# SCH_CH1616ADX_2022-05-06.net
KiCad netlist of a schematic drawn in EasyEDA
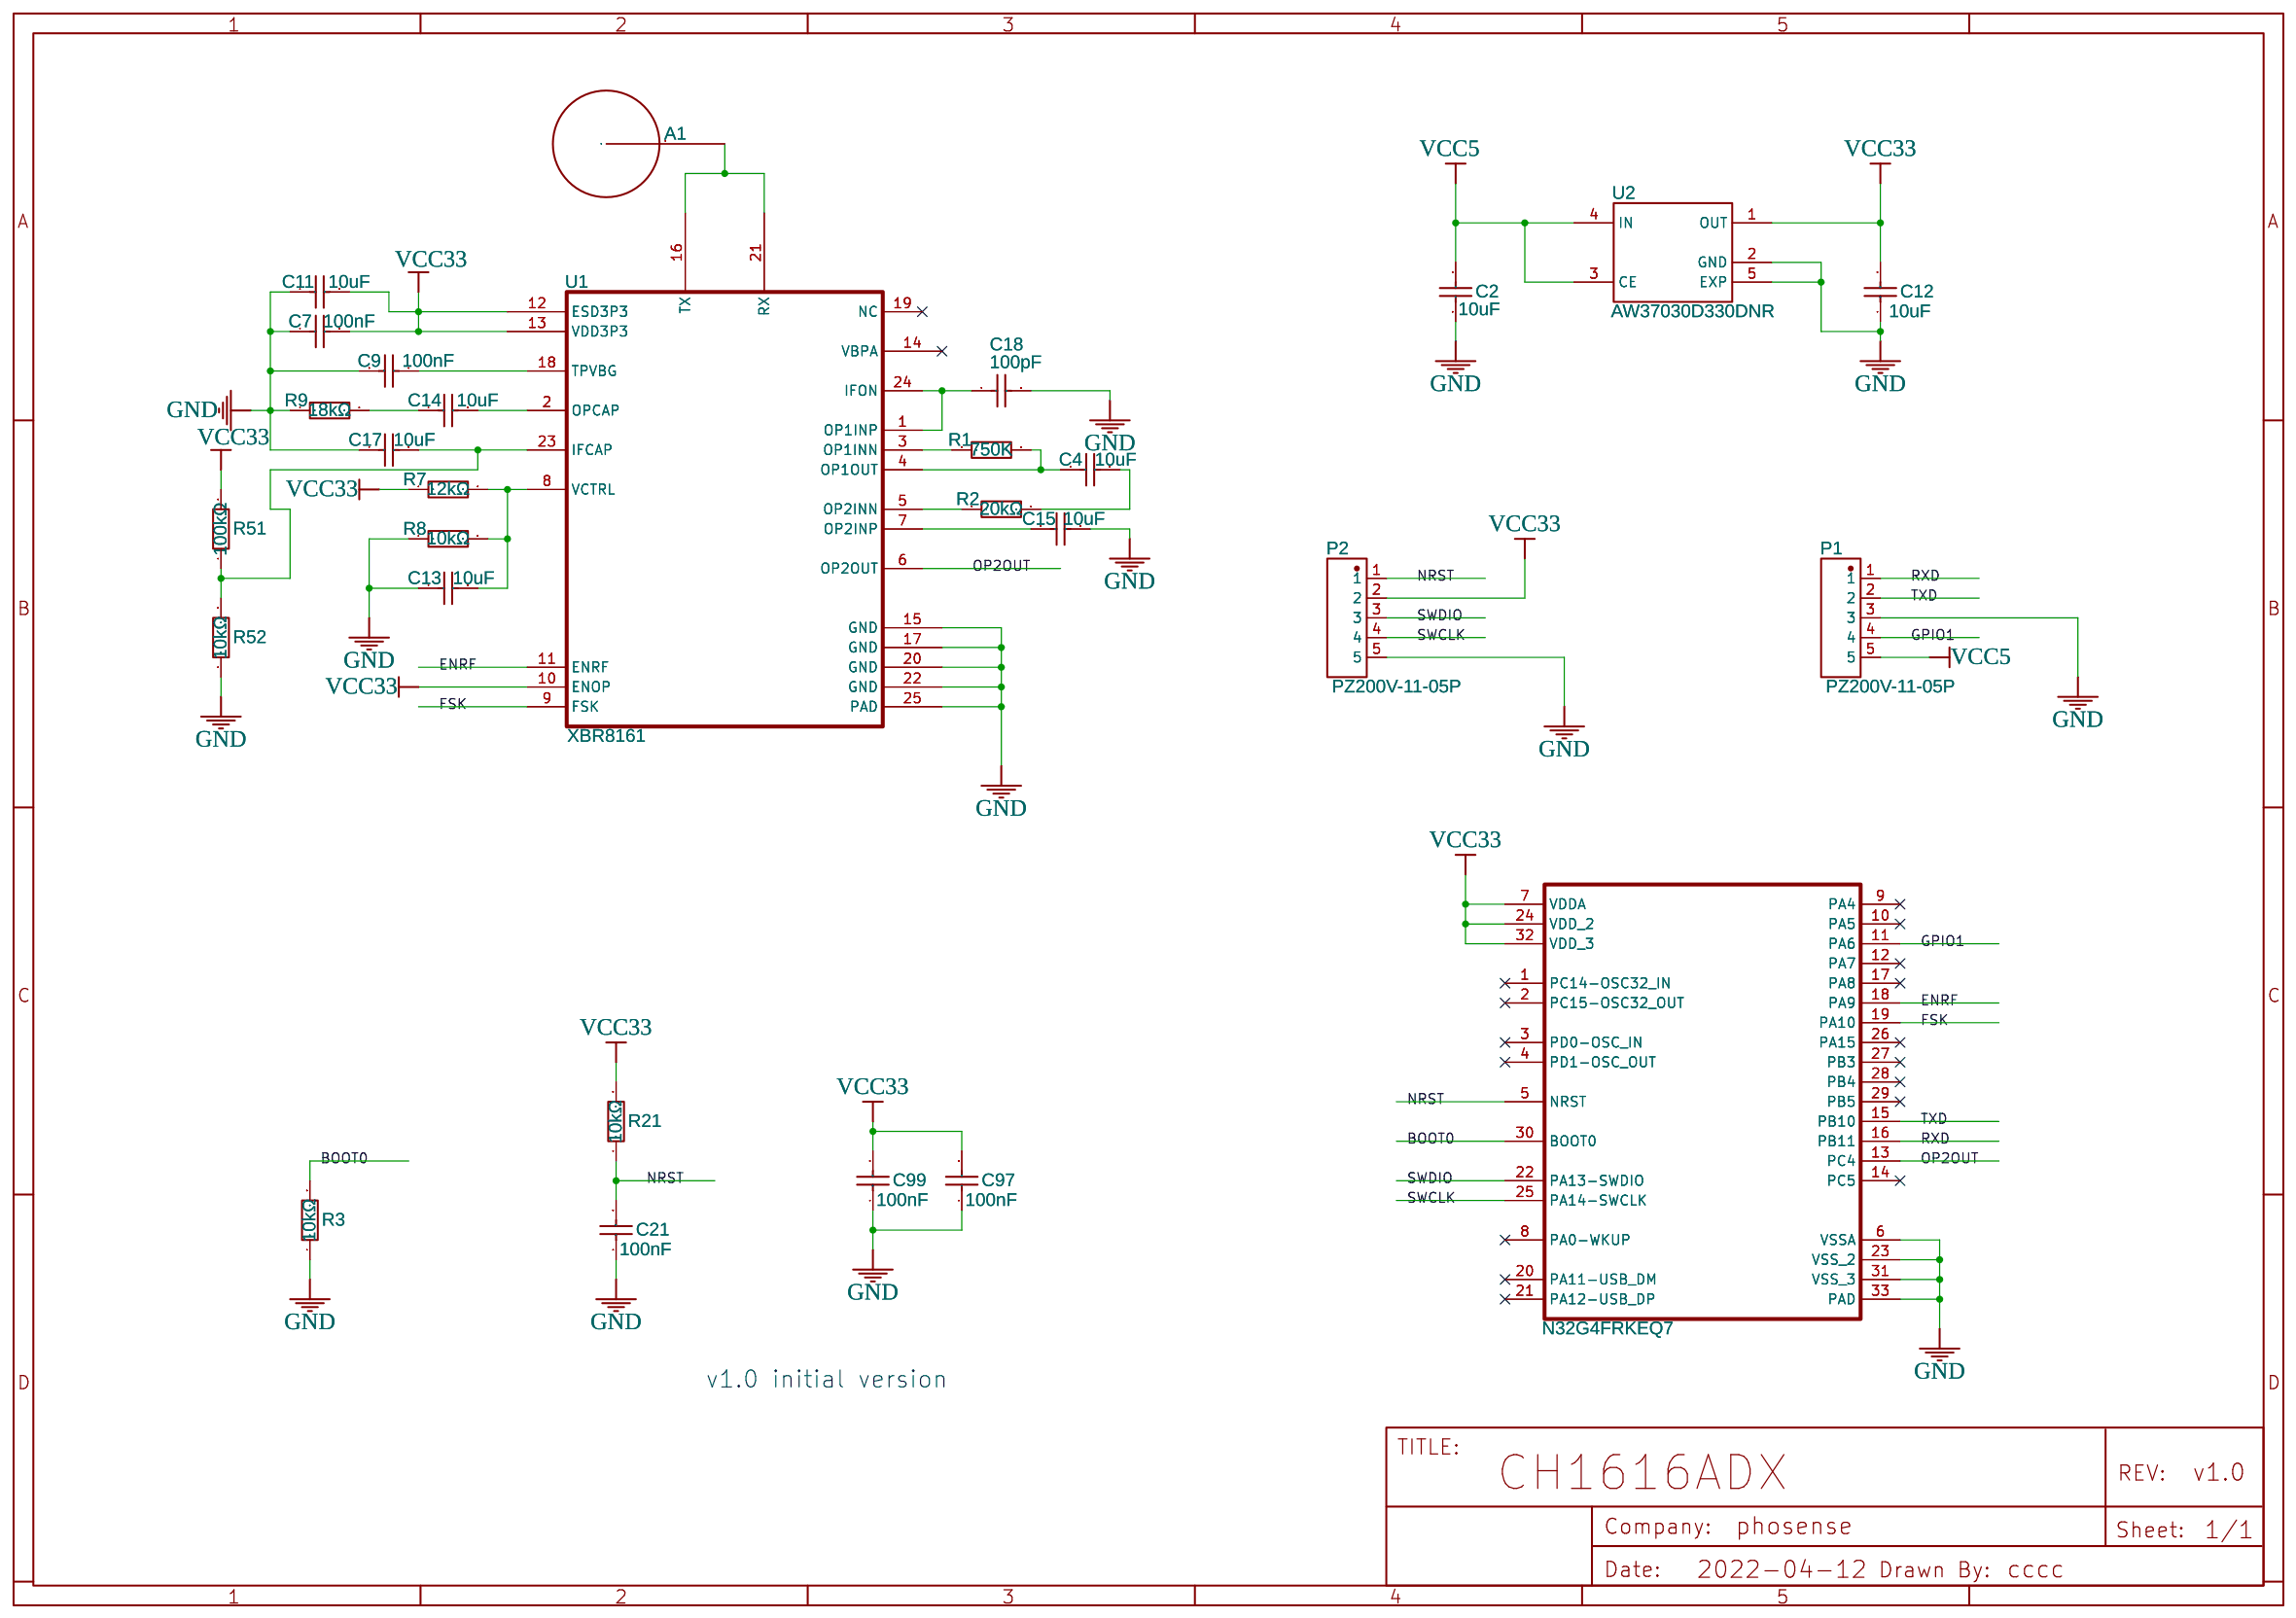
[diagram p0: schematic sheet]

(export (version "E")
  (design (tool "Eeschema 10.0.6"))
  (components
    (comp (ref "A1") (value "ar_10.525G") (libsource (lib "") (part "ar_10.525G")))
    (comp (ref "C2")
      (value "10uF")
      (fields
        (field (name "BOM_Manufacturer Part") "CL05A106MQ5NUNC")
        (field (name "BOM_Supplier Part") "C15525")
      )
      (libsource (lib "") (part "CL05A106MQ5NUNC_2"))
    )
    (comp (ref "C4")
      (value "10uF")
      (fields
        (field (name "BOM_Manufacturer Part") "CL05A106MQ5NUNC")
        (field (name "BOM_Supplier Part") "C15525")
      )
      (libsource (lib "") (part "CL05A106MQ5NUNC_1"))
    )
    (comp (ref "C7")
      (value "100nF")
      (fields
        (field (name "BOM_Manufacturer Part") "CL05B104KO5NNNC")
        (field (name "BOM_Supplier Part") "C1525")
      )
      (libsource (lib "") (part "CL05B104KO5NNNC_2"))
    )
    (comp (ref "C9")
      (value "100nF")
      (fields
        (field (name "BOM_Manufacturer Part") "CL05B104KO5NNNC")
        (field (name "BOM_Supplier Part") "C1525")
      )
      (libsource (lib "") (part "CL05B104KO5NNNC_1"))
    )
    (comp (ref "C11")
      (value "10uF")
      (fields
        (field (name "BOM_Manufacturer Part") "CL05A106MQ5NUNC")
        (field (name "BOM_Supplier Part") "C15525")
      )
      (libsource (lib "") (part "CL05A106MQ5NUNC_1"))
    )
    (comp (ref "C12")
      (value "10uF")
      (fields
        (field (name "BOM_Manufacturer Part") "CL05A106MQ5NUNC")
        (field (name "BOM_Supplier Part") "C15525")
      )
      (libsource (lib "") (part "CL05A106MQ5NUNC"))
    )
    (comp (ref "C13")
      (value "10uF")
      (fields
        (field (name "BOM_Manufacturer Part") "CL05A106MQ5NUNC")
        (field (name "BOM_Supplier Part") "C15525")
      )
      (libsource (lib "") (part "CL05A106MQ5NUNC_1"))
    )
    (comp (ref "C14")
      (value "10uF")
      (fields
        (field (name "BOM_Manufacturer Part") "CL05A106MQ5NUNC")
        (field (name "BOM_Supplier Part") "C15525")
      )
      (libsource (lib "") (part "CL05A106MQ5NUNC_1"))
    )
    (comp (ref "C15")
      (value "10uF")
      (fields
        (field (name "BOM_Manufacturer Part") "CL05A106MQ5NUNC")
        (field (name "BOM_Supplier Part") "C15525")
      )
      (libsource (lib "") (part "CL05A106MQ5NUNC_1"))
    )
    (comp (ref "C17")
      (value "10uF")
      (fields
        (field (name "BOM_Manufacturer Part") "CL05A106MQ5NUNC")
        (field (name "BOM_Supplier Part") "C15525")
      )
      (libsource (lib "") (part "CL05A106MQ5NUNC_1"))
    )
    (comp (ref "C18")
      (value "100pF")
      (fields
        (field (name "BOM_Manufacturer Part") "0402CG101J500NT")
        (field (name "BOM_Supplier Part") "C1546")
      )
      (libsource (lib "") (part "0402CG101J500NT"))
    )
    (comp (ref "C21")
      (value "100nF")
      (fields
        (field (name "BOM_Manufacturer Part") "CL05B104KO5NNNC")
        (field (name "BOM_Supplier Part") "C1525")
      )
      (libsource (lib "") (part "CL05B104KO5NNNC"))
    )
    (comp (ref "C97")
      (value "100nF")
      (fields
        (field (name "BOM_Manufacturer Part") "CL05B104KO5NNNC")
        (field (name "BOM_Supplier Part") "C1525")
      )
      (libsource (lib "") (part "CL05B104KO5NNNC"))
    )
    (comp (ref "C99")
      (value "100nF")
      (fields
        (field (name "BOM_Manufacturer Part") "CL05B104KO5NNNC")
        (field (name "BOM_Supplier Part") "C1525")
      )
      (libsource (lib "") (part "CL05B104KO5NNNC"))
    )
    (comp (ref "NO1") (value "N32G4FRKEQ7") (libsource (lib "") (part "N32G4FRKEQ7")))
    (comp (ref "P1")
      (value "PZ200V-11-05P")
      (fields (field (name "BOM_Supplier Part") "C541859"))
      (libsource (lib "") (part "PZ200V-11-05P"))
    )
    (comp (ref "P2")
      (value "PZ200V-11-05P")
      (fields (field (name "BOM_Supplier Part") "C541859"))
      (libsource (lib "") (part "PZ200V-11-05P"))
    )
    (comp (ref "R1")
      (value "750K")
      (fields
        (field (name "BOM_Manufacturer Part") "AC0402JR-07750KL")
        (field (name "BOM_Supplier Part") "C227414")
      )
      (libsource (lib "") (part "AC0402JR-07750KL"))
    )
    (comp (ref "R2")
      (value "20kΩ")
      (fields
        (field (name "BOM_Manufacturer Part") "0402WGF2002TCE")
        (field (name "BOM_Supplier Part") "C25765")
      )
      (libsource (lib "") (part "0402WGF2002TCE"))
    )
    (comp (ref "R3")
      (value "10kΩ")
      (fields
        (field (name "BOM_Manufacturer Part") "0402WGF1002TCE")
        (field (name "BOM_Supplier Part") "C25744")
      )
      (libsource (lib "") (part "0402WGF1002TCE"))
    )
    (comp (ref "R7")
      (value "12kΩ")
      (fields
        (field (name "BOM_Manufacturer Part") "0402WGF1202TCE")
        (field (name "BOM_Supplier Part") "C25752")
      )
      (libsource (lib "") (part "0402WGF1202TCE"))
    )
    (comp (ref "R8")
      (value "10kΩ")
      (fields
        (field (name "BOM_Manufacturer Part") "0402WGF1002TCE")
        (field (name "BOM_Supplier Part") "C25744")
      )
      (libsource (lib "") (part "0402WGF1002TCE_1"))
    )
    (comp (ref "R9")
      (value "18kΩ")
      (fields
        (field (name "BOM_Manufacturer Part") "0402WGF1802TCE")
        (field (name "BOM_Supplier Part") "C25762")
      )
      (libsource (lib "") (part "0402WGF1802TCE"))
    )
    (comp (ref "R21")
      (value "10kΩ")
      (fields
        (field (name "BOM_Manufacturer Part") "0402WGF1002TCE")
        (field (name "BOM_Supplier Part") "C25744")
      )
      (libsource (lib "") (part "0402WGF1002TCE"))
    )
    (comp (ref "R51")
      (value "100kΩ")
      (fields
        (field (name "BOM_Manufacturer Part") "0402WGF1003TCE")
        (field (name "BOM_Supplier Part") "C25741")
      )
      (libsource (lib "") (part "0402WGF1003TCE"))
    )
    (comp (ref "R52")
      (value "10kΩ")
      (fields
        (field (name "BOM_Manufacturer Part") "0402WGF1002TCE")
        (field (name "BOM_Supplier Part") "C25744")
      )
      (libsource (lib "") (part "0402WGF1002TCE"))
    )
    (comp (ref "U1") (value "XBR8161") (libsource (lib "") (part "XBR8161")))
    (comp (ref "U2") (value "AW37030D330DNR") (libsource (lib "") (part "AW37030D330DNR")))
  )
  (nets
    (net (code "1") (name "/BOOT0") (class "Default")
      (node (ref "NO1") (pin "30") (pinfunction "BOOT0_30") (pintype "unspecified"))
      (node (ref "R3") (pin "2") (pinfunction "2_2") (pintype "input"))
    )
    (net (code "2") (name "/ENRF") (class "Default")
      (node (ref "NO1") (pin "18") (pinfunction "PA9_18") (pintype "unspecified"))
      (node (ref "U1") (pin "11") (pinfunction "ENRF_11") (pintype "unspecified"))
    )
    (net (code "3") (name "/FSK") (class "Default")
      (node (ref "NO1") (pin "19") (pinfunction "PA10_19") (pintype "unspecified"))
      (node (ref "U1") (pin "9") (pinfunction "FSK_9") (pintype "unspecified"))
    )
    (net (code "4") (name "/GPIO1") (class "Default")
      (node (ref "NO1") (pin "11") (pinfunction "PA6_11") (pintype "unspecified"))
      (node (ref "P1") (pin "4") (pinfunction "4_4") (pintype "unspecified"))
    )
    (net (code "5") (name "/NRST") (class "Default")
      (node (ref "C21") (pin "2") (pinfunction "2_2") (pintype "input"))
      (node (ref "NO1") (pin "5") (pinfunction "NRST_5") (pintype "input"))
      (node (ref "P2") (pin "1") (pinfunction "1_1") (pintype "unspecified"))
      (node (ref "R21") (pin "1") (pinfunction "1_1") (pintype "input"))
    )
    (net (code "6") (name "/OP2OUT") (class "Default")
      (node (ref "NO1") (pin "13") (pinfunction "PC4_13") (pintype "unspecified"))
      (node (ref "U1") (pin "6") (pinfunction "OP2OUT_6") (pintype "unspecified"))
    )
    (net (code "7") (name "/RXD") (class "Default")
      (node (ref "NO1") (pin "16") (pinfunction "PB11_16") (pintype "unspecified"))
      (node (ref "P1") (pin "1") (pinfunction "1_1") (pintype "unspecified"))
    )
    (net (code "8") (name "/SWCLK") (class "Default")
      (node (ref "NO1") (pin "25") (pinfunction "PA14-SWCLK_25") (pintype "unspecified"))
      (node (ref "P2") (pin "4") (pinfunction "4_4") (pintype "unspecified"))
    )
    (net (code "9") (name "/SWDIO") (class "Default")
      (node (ref "NO1") (pin "22") (pinfunction "PA13-SWDIO_22") (pintype "unspecified"))
      (node (ref "P2") (pin "3") (pinfunction "3_3") (pintype "unspecified"))
    )
    (net (code "10") (name "/TXD") (class "Default")
      (node (ref "NO1") (pin "15") (pinfunction "PB10_15") (pintype "unspecified"))
      (node (ref "P1") (pin "2") (pinfunction "2_2") (pintype "unspecified"))
    )
    (net (code "11") (name "GND") (class "Default")
      (node (ref "C11") (pin "1") (pinfunction "1_1") (pintype "input"))
      (node (ref "C12") (pin "1") (pinfunction "1_1") (pintype "input"))
      (node (ref "C13") (pin "1") (pinfunction "1_1") (pintype "input"))
      (node (ref "C15") (pin "2") (pinfunction "2_2") (pintype "input"))
      (node (ref "C17") (pin "1") (pinfunction "1_1") (pintype "input"))
      (node (ref "C18") (pin "2") (pinfunction "2_2") (pintype "input"))
      (node (ref "C2") (pin "2") (pinfunction "2_2") (pintype "input"))
      (node (ref "C21") (pin "1") (pinfunction "1_1") (pintype "input"))
      (node (ref "C7") (pin "1") (pinfunction "1_1") (pintype "input"))
      (node (ref "C9") (pin "2") (pinfunction "2_2") (pintype "input"))
      (node (ref "C97") (pin "1") (pinfunction "1_1") (pintype "input"))
      (node (ref "C99") (pin "1") (pinfunction "1_1") (pintype "input"))
      (node (ref "NO1") (pin "23") (pinfunction "VSS_2_23") (pintype "passive"))
      (node (ref "NO1") (pin "31") (pinfunction "VSS_3_31") (pintype "passive"))
      (node (ref "NO1") (pin "33") (pinfunction "PAD_33") (pintype "passive"))
      (node (ref "NO1") (pin "6") (pinfunction "VSSA_6") (pintype "passive"))
      (node (ref "P1") (pin "3") (pinfunction "3_3") (pintype "unspecified"))
      (node (ref "P2") (pin "5") (pinfunction "5_5") (pintype "unspecified"))
      (node (ref "R3") (pin "1") (pinfunction "1_1") (pintype "input"))
      (node (ref "R52") (pin "1") (pinfunction "1_1") (pintype "input"))
      (node (ref "R8") (pin "1") (pinfunction "1_1") (pintype "input"))
      (node (ref "R9") (pin "1") (pinfunction "1_1") (pintype "input"))
      (node (ref "U1") (pin "15") (pinfunction "GND_15") (pintype "unspecified"))
      (node (ref "U1") (pin "17") (pinfunction "GND_17") (pintype "unspecified"))
      (node (ref "U1") (pin "20") (pinfunction "GND_20") (pintype "unspecified"))
      (node (ref "U1") (pin "22") (pinfunction "GND_22") (pintype "unspecified"))
      (node (ref "U1") (pin "25") (pinfunction "PAD_25") (pintype "unspecified"))
      (node (ref "U2") (pin "2") (pinfunction "GND_2") (pintype "unspecified"))
      (node (ref "U2") (pin "5") (pinfunction "EXP_5") (pintype "unspecified"))
    )
    (net (code "12") (name "Net-(C4-Pad2)") (class "Default")
      (node (ref "C4") (pin "2") (pinfunction "2_2") (pintype "input"))
      (node (ref "R2") (pin "2") (pinfunction "2_2") (pintype "input"))
    )
    (net (code "13") (name "Net-(C14-Pad1)") (class "Default")
      (node (ref "C14") (pin "1") (pinfunction "1_1") (pintype "input"))
      (node (ref "R9") (pin "2") (pinfunction "2_2") (pintype "input"))
    )
    (net (code "14") (name "Net-(U1-IFCAP)") (class "Default")
      (node (ref "C17") (pin "2") (pinfunction "2_2") (pintype "input"))
      (node (ref "R51") (pin "1") (pinfunction "1_1") (pintype "input"))
      (node (ref "R52") (pin "2") (pinfunction "2_2") (pintype "input"))
      (node (ref "U1") (pin "23") (pinfunction "IFCAP_23") (pintype "unspecified"))
    )
    (net (code "15") (name "Net-(U1-IFON)") (class "Default")
      (node (ref "C18") (pin "1") (pinfunction "1_1") (pintype "input"))
      (node (ref "U1") (pin "1") (pinfunction "OP1INP_1") (pintype "unspecified"))
      (node (ref "U1") (pin "24") (pinfunction "IFON_24") (pintype "unspecified"))
    )
    (net (code "16") (name "Net-(U1-OP1INN)") (class "Default")
      (node (ref "R1") (pin "1") (pinfunction "1_1") (pintype "unspecified"))
      (node (ref "U1") (pin "3") (pinfunction "OP1INN_3") (pintype "unspecified"))
    )
    (net (code "17") (name "Net-(U1-OP1OUT)") (class "Default")
      (node (ref "C4") (pin "1") (pinfunction "1_1") (pintype "input"))
      (node (ref "R1") (pin "2") (pinfunction "2_2") (pintype "unspecified"))
      (node (ref "U1") (pin "4") (pinfunction "OP1OUT_4") (pintype "unspecified"))
    )
    (net (code "18") (name "Net-(U1-OP2INN)") (class "Default")
      (node (ref "R2") (pin "1") (pinfunction "1_1") (pintype "input"))
      (node (ref "U1") (pin "5") (pinfunction "OP2INN_5") (pintype "unspecified"))
    )
    (net (code "19") (name "Net-(U1-OP2INP)") (class "Default")
      (node (ref "C15") (pin "1") (pinfunction "1_1") (pintype "input"))
      (node (ref "U1") (pin "7") (pinfunction "OP2INP_7") (pintype "unspecified"))
    )
    (net (code "20") (name "Net-(U1-OPCAP)") (class "Default")
      (node (ref "C14") (pin "2") (pinfunction "2_2") (pintype "input"))
      (node (ref "U1") (pin "2") (pinfunction "OPCAP_2") (pintype "unspecified"))
    )
    (net (code "21") (name "Net-(U1-RX)") (class "Default")
      (node (ref "A1") (pin "1") (pinfunction "1_1") (pintype "unspecified"))
      (node (ref "U1") (pin "16") (pinfunction "TX_16") (pintype "unspecified"))
      (node (ref "U1") (pin "21") (pinfunction "RX_21") (pintype "unspecified"))
    )
    (net (code "22") (name "Net-(U1-TPVBG)") (class "Default")
      (node (ref "C9") (pin "1") (pinfunction "1_1") (pintype "input"))
      (node (ref "U1") (pin "18") (pinfunction "TPVBG_18") (pintype "unspecified"))
    )
    (net (code "23") (name "Net-(U1-VCTRL)") (class "Default")
      (node (ref "C13") (pin "2") (pinfunction "2_2") (pintype "input"))
      (node (ref "R7") (pin "2") (pinfunction "2_2") (pintype "input"))
      (node (ref "R8") (pin "2") (pinfunction "2_2") (pintype "input"))
      (node (ref "U1") (pin "8") (pinfunction "VCTRL_8") (pintype "unspecified"))
    )
    (net (code "24") (name "VCC5") (class "Default")
      (node (ref "C2") (pin "1") (pinfunction "1_1") (pintype "input"))
      (node (ref "P1") (pin "5") (pinfunction "5_5") (pintype "unspecified"))
      (node (ref "U2") (pin "3") (pinfunction "CE_3") (pintype "unspecified"))
      (node (ref "U2") (pin "4") (pinfunction "IN_4") (pintype "unspecified"))
    )
    (net (code "25") (name "VCC33") (class "Default")
      (node (ref "C11") (pin "2") (pinfunction "2_2") (pintype "input"))
      (node (ref "C12") (pin "2") (pinfunction "2_2") (pintype "input"))
      (node (ref "C7") (pin "2") (pinfunction "2_2") (pintype "input"))
      (node (ref "C97") (pin "2") (pinfunction "2_2") (pintype "input"))
      (node (ref "C99") (pin "2") (pinfunction "2_2") (pintype "input"))
      (node (ref "NO1") (pin "24") (pinfunction "VDD_2_24") (pintype "passive"))
      (node (ref "NO1") (pin "32") (pinfunction "VDD_3_32") (pintype "passive"))
      (node (ref "NO1") (pin "7") (pinfunction "VDDA_7") (pintype "passive"))
      (node (ref "P2") (pin "2") (pinfunction "2_2") (pintype "unspecified"))
      (node (ref "R21") (pin "2") (pinfunction "2_2") (pintype "input"))
      (node (ref "R51") (pin "2") (pinfunction "2_2") (pintype "input"))
      (node (ref "R7") (pin "1") (pinfunction "1_1") (pintype "input"))
      (node (ref "U1") (pin "10") (pinfunction "ENOP_10") (pintype "unspecified"))
      (node (ref "U1") (pin "12") (pinfunction "ESD3P3_12") (pintype "unspecified"))
      (node (ref "U1") (pin "13") (pinfunction "VDD3P3_13") (pintype "unspecified"))
      (node (ref "U2") (pin "1") (pinfunction "OUT_1") (pintype "unspecified"))
    )
    (net (code "26") (name "unconnected-(NO1-PA0-WKUP-Pad8)") (class "Default")
      (node (ref "NO1") (pin "8") (pinfunction "PA0-WKUP_8") (pintype "unspecified+no_connect"))
    )
    (net (code "27") (name "unconnected-(NO1-PA4-Pad9)") (class "Default")
      (node (ref "NO1") (pin "9") (pinfunction "PA4_9") (pintype "unspecified+no_connect"))
    )
    (net (code "28") (name "unconnected-(NO1-PA5-Pad10)") (class "Default")
      (node (ref "NO1") (pin "10") (pinfunction "PA5_10") (pintype "unspecified+no_connect"))
    )
    (net (code "29") (name "unconnected-(NO1-PA7-Pad12)") (class "Default")
      (node (ref "NO1") (pin "12") (pinfunction "PA7_12") (pintype "unspecified+no_connect"))
    )
    (net (code "30") (name "unconnected-(NO1-PA8-Pad17)") (class "Default")
      (node (ref "NO1") (pin "17") (pinfunction "PA8_17") (pintype "unspecified+no_connect"))
    )
    (net (code "31") (name "unconnected-(NO1-PA11-USB_DM-Pad20)") (class "Default")
      (node (ref "NO1") (pin "20") (pinfunction "PA11-USB_DM_20") (pintype "unspecified+no_connect"))
    )
    (net (code "32") (name "unconnected-(NO1-PA12-USB_DP-Pad21)") (class "Default")
      (node (ref "NO1") (pin "21") (pinfunction "PA12-USB_DP_21") (pintype "unspecified+no_connect"))
    )
    (net (code "33") (name "unconnected-(NO1-PA15-Pad26)") (class "Default")
      (node (ref "NO1") (pin "26") (pinfunction "PA15_26") (pintype "unspecified+no_connect"))
    )
    (net (code "34") (name "unconnected-(NO1-PB3-Pad27)") (class "Default")
      (node (ref "NO1") (pin "27") (pinfunction "PB3_27") (pintype "unspecified+no_connect"))
    )
    (net (code "35") (name "unconnected-(NO1-PB4-Pad28)") (class "Default")
      (node (ref "NO1") (pin "28") (pinfunction "PB4_28") (pintype "unspecified+no_connect"))
    )
    (net (code "36") (name "unconnected-(NO1-PB5-Pad29)") (class "Default")
      (node (ref "NO1") (pin "29") (pinfunction "PB5_29") (pintype "unspecified+no_connect"))
    )
    (net (code "37") (name "unconnected-(NO1-PC5-Pad14)") (class "Default")
      (node (ref "NO1") (pin "14") (pinfunction "PC5_14") (pintype "unspecified+no_connect"))
    )
    (net (code "38") (name "unconnected-(NO1-PC14-OSC32_IN-Pad1)") (class "Default")
      (node (ref "NO1") (pin "1") (pinfunction "PC14-OSC32_IN_1") (pintype "unspecified+no_connect"))
    )
    (net (code "39") (name "unconnected-(NO1-PC15-OSC32_OUT-Pad2)") (class "Default")
      (node (ref "NO1") (pin "2") (pinfunction "PC15-OSC32_OUT_2") (pintype "unspecified+no_connect"))
    )
    (net (code "40") (name "unconnected-(NO1-PD0-OSC_IN-Pad3)") (class "Default")
      (node (ref "NO1") (pin "3") (pinfunction "PD0-OSC_IN_3") (pintype "unspecified+no_connect"))
    )
    (net (code "41") (name "unconnected-(NO1-PD1-OSC_OUT-Pad4)") (class "Default")
      (node (ref "NO1") (pin "4") (pinfunction "PD1-OSC_OUT_4") (pintype "unspecified+no_connect"))
    )
    (net (code "42") (name "unconnected-(U1-NC-Pad19)") (class "Default")
      (node (ref "U1") (pin "19") (pinfunction "NC_19") (pintype "unspecified+no_connect"))
    )
    (net (code "43") (name "unconnected-(U1-VBPA-Pad14)") (class "Default")
      (node (ref "U1") (pin "14") (pinfunction "VBPA_14") (pintype "unspecified+no_connect"))
    )
  )
)
